# MOS-2.net
KiCad netlist of a schematic drawn in EAGLE
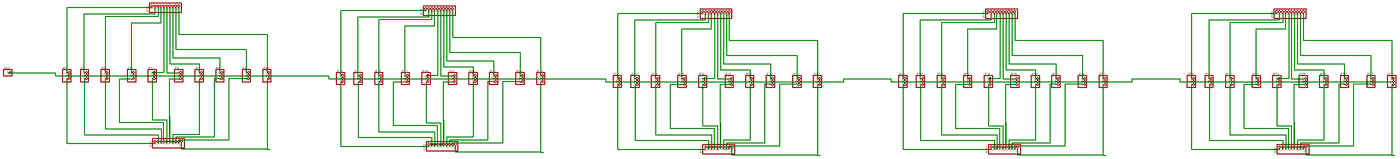
[diagram p0: schematic, sheet 1, overview]
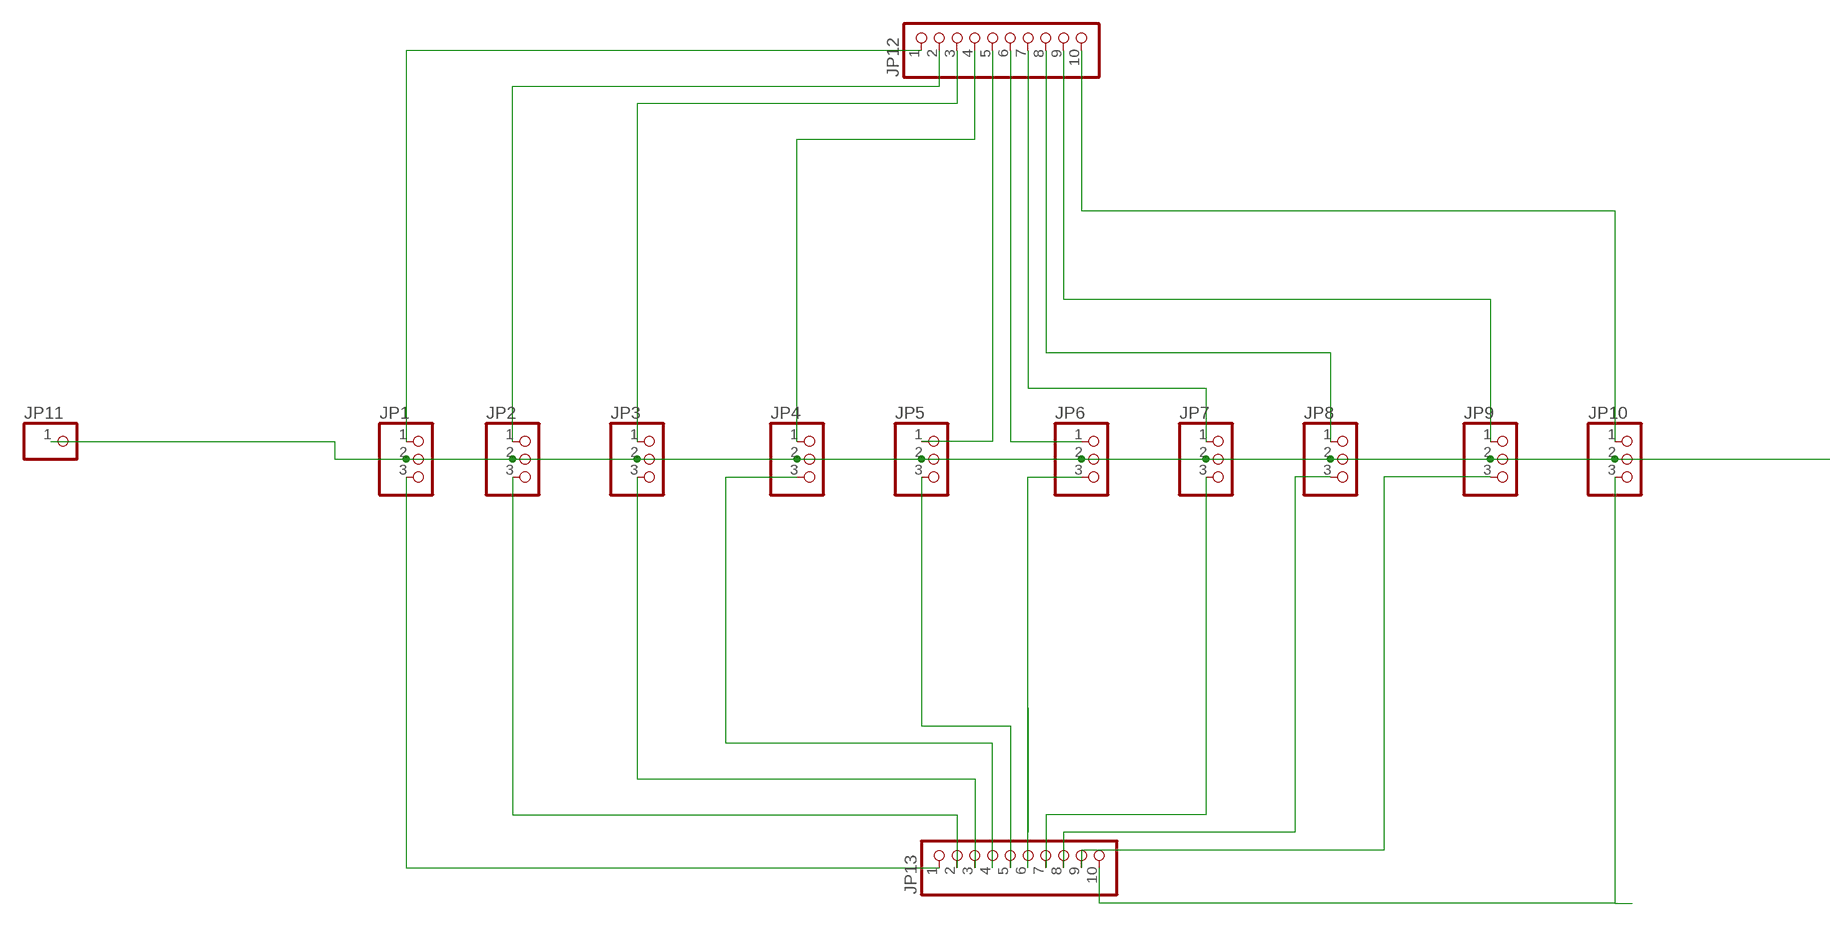
[diagram p1: schematic, sheet 1, part 1 of 4]
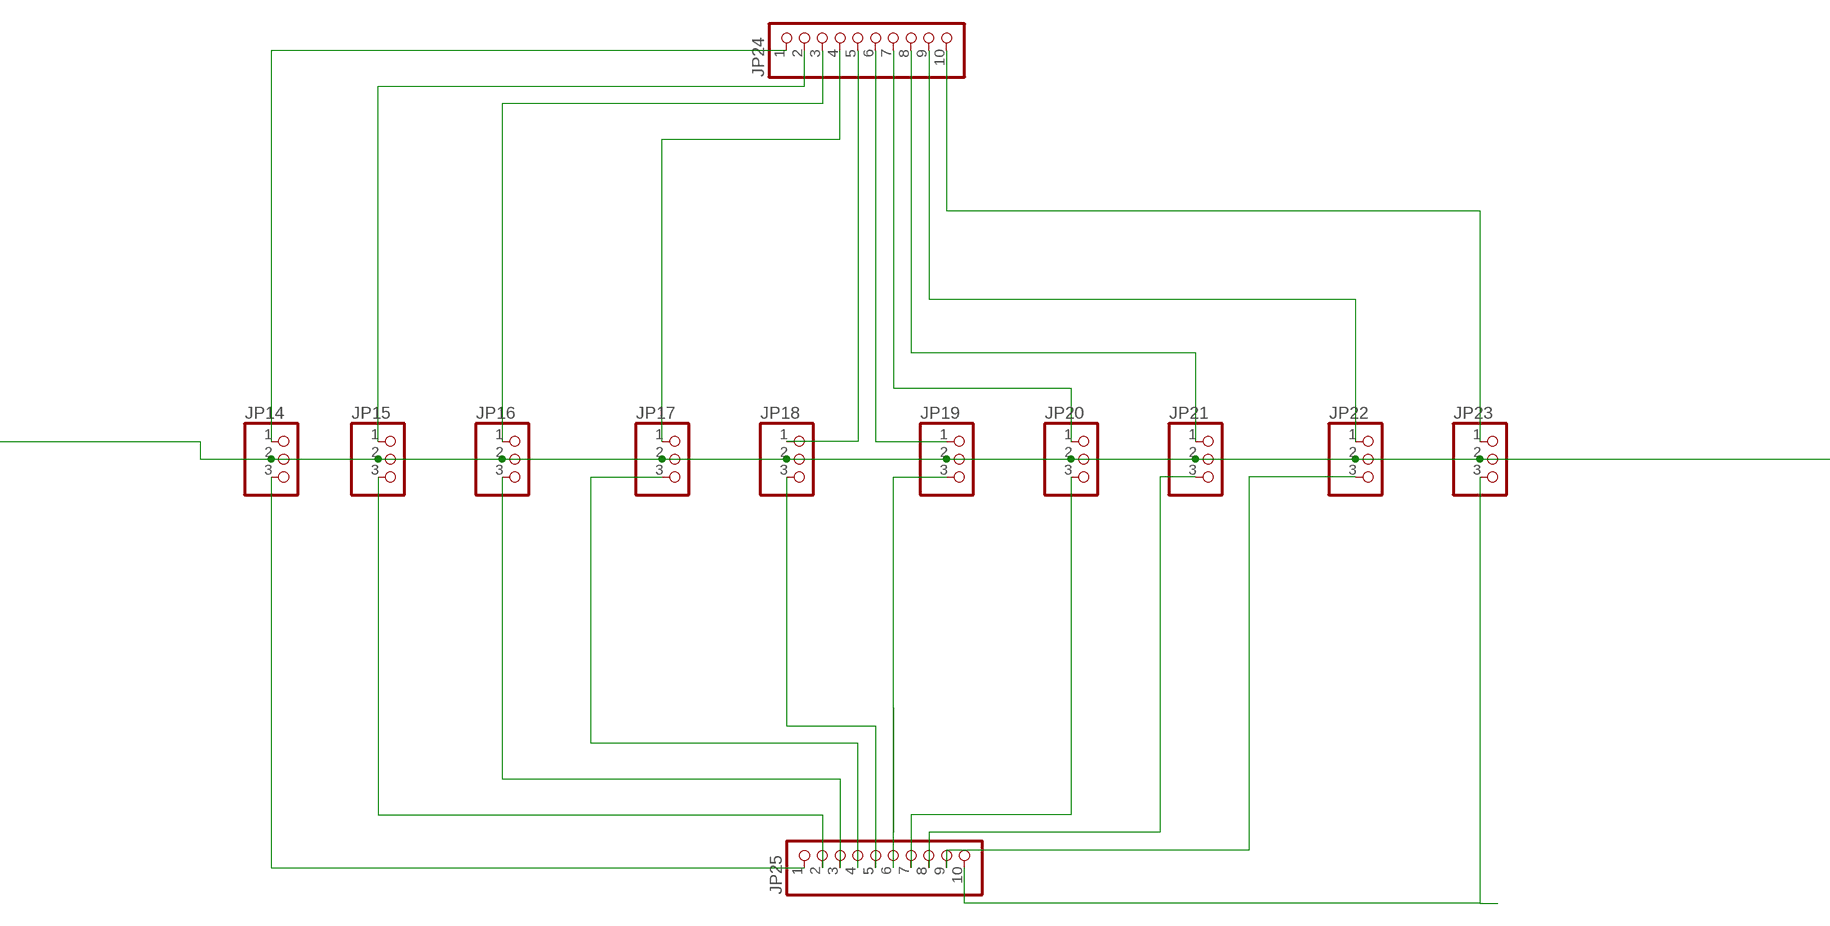
[diagram p2: schematic, sheet 1, part 2 of 4]
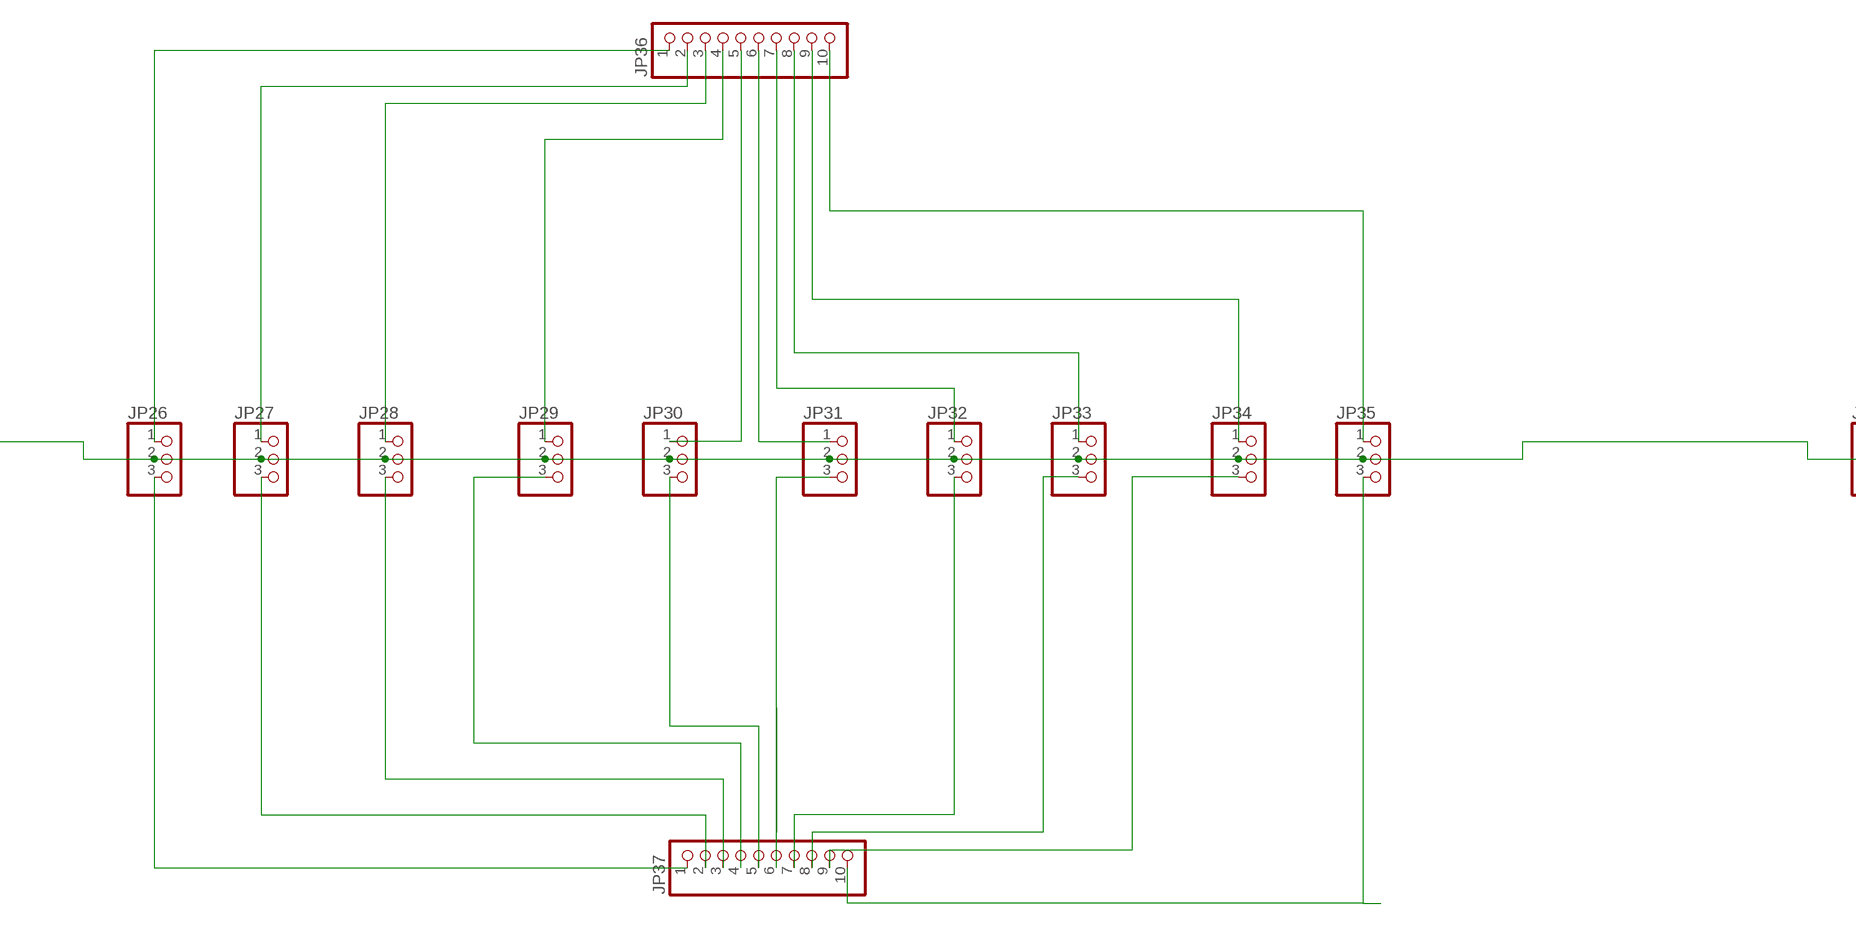
[diagram p3: schematic, sheet 1, part 3 of 4]
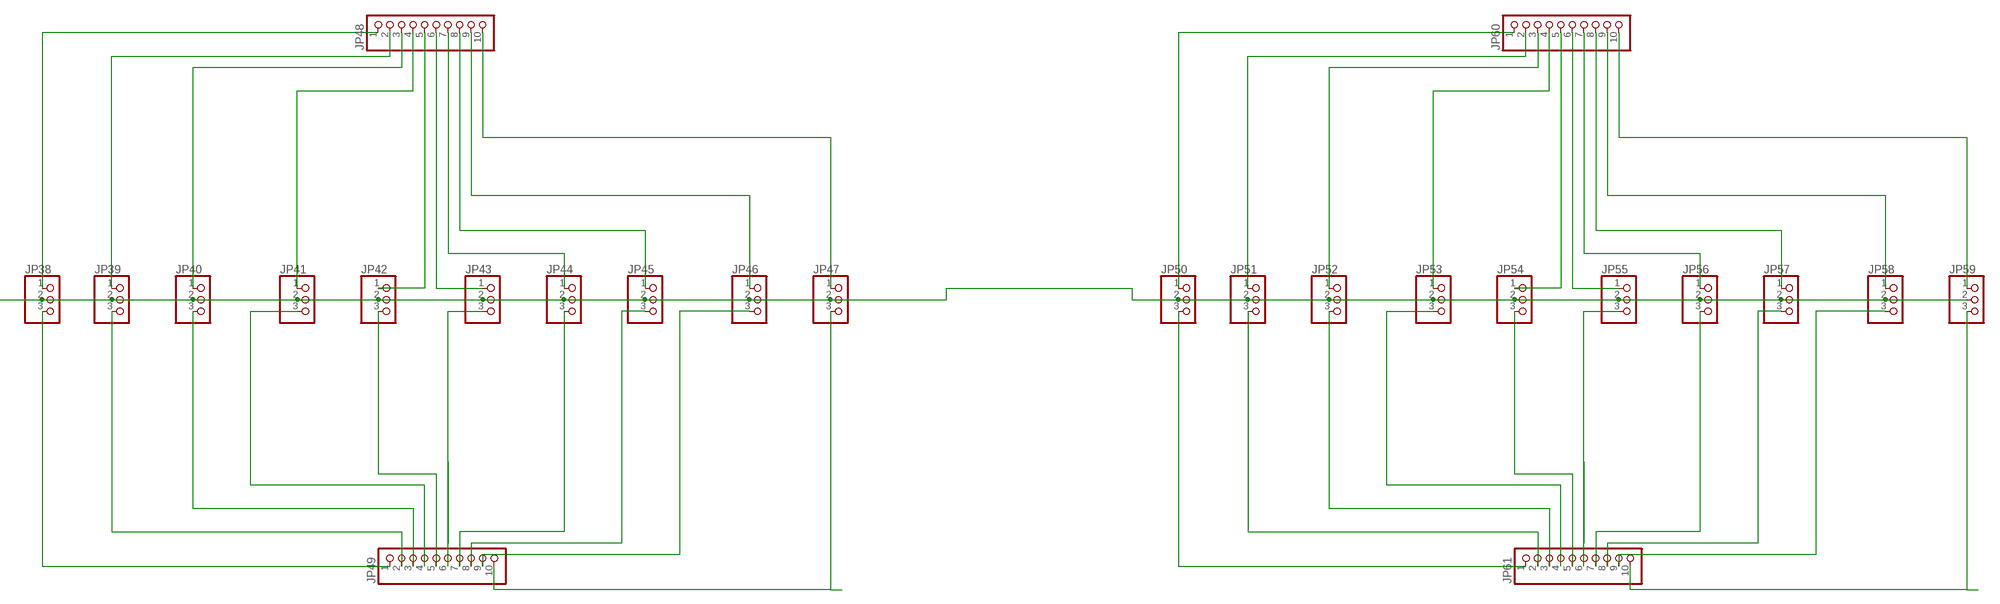
[diagram p4: schematic, sheet 1, part 4 of 4]

(export (version "E")
  (design (tool "Eeschema 10.0.6"))
  (components
    (comp (ref "JP1")
      (value "PINHD-1X3")
      (footprint "eagle-import:1X03")
      (libsource (lib "eagle-import") (part "PINHD-1X3"))
    )
    (comp (ref "JP2")
      (value "PINHD-1X3")
      (footprint "eagle-import:1X03")
      (libsource (lib "eagle-import") (part "PINHD-1X3"))
    )
    (comp (ref "JP3")
      (value "PINHD-1X3")
      (footprint "eagle-import:1X03")
      (libsource (lib "eagle-import") (part "PINHD-1X3"))
    )
    (comp (ref "JP4")
      (value "PINHD-1X3")
      (footprint "eagle-import:1X03")
      (libsource (lib "eagle-import") (part "PINHD-1X3"))
    )
    (comp (ref "JP5")
      (value "PINHD-1X3")
      (footprint "eagle-import:1X03")
      (libsource (lib "eagle-import") (part "PINHD-1X3"))
    )
    (comp (ref "JP6")
      (value "PINHD-1X3")
      (footprint "eagle-import:1X03")
      (libsource (lib "eagle-import") (part "PINHD-1X3"))
    )
    (comp (ref "JP7")
      (value "PINHD-1X3")
      (footprint "eagle-import:1X03")
      (libsource (lib "eagle-import") (part "PINHD-1X3"))
    )
    (comp (ref "JP8")
      (value "PINHD-1X3")
      (footprint "eagle-import:1X03")
      (libsource (lib "eagle-import") (part "PINHD-1X3"))
    )
    (comp (ref "JP9")
      (value "PINHD-1X3")
      (footprint "eagle-import:1X03")
      (libsource (lib "eagle-import") (part "PINHD-1X3"))
    )
    (comp (ref "JP10")
      (value "PINHD-1X3")
      (footprint "eagle-import:1X03")
      (libsource (lib "eagle-import") (part "PINHD-1X3"))
    )
    (comp (ref "JP11")
      (value "PINHD-1X1")
      (footprint "eagle-import:1X01")
      (libsource (lib "eagle-import") (part "PINHD-1X1"))
    )
    (comp (ref "JP12")
      (value "PINHD-1X10")
      (footprint "eagle-import:1X10")
      (libsource (lib "eagle-import") (part "PINHD-1X10"))
    )
    (comp (ref "JP13")
      (value "PINHD-1X10")
      (footprint "eagle-import:1X10")
      (libsource (lib "eagle-import") (part "PINHD-1X10"))
    )
    (comp (ref "JP14")
      (value "PINHD-1X3")
      (footprint "eagle-import:1X03")
      (libsource (lib "eagle-import") (part "PINHD-1X3"))
    )
    (comp (ref "JP15")
      (value "PINHD-1X3")
      (footprint "eagle-import:1X03")
      (libsource (lib "eagle-import") (part "PINHD-1X3"))
    )
    (comp (ref "JP16")
      (value "PINHD-1X3")
      (footprint "eagle-import:1X03")
      (libsource (lib "eagle-import") (part "PINHD-1X3"))
    )
    (comp (ref "JP17")
      (value "PINHD-1X3")
      (footprint "eagle-import:1X03")
      (libsource (lib "eagle-import") (part "PINHD-1X3"))
    )
    (comp (ref "JP18")
      (value "PINHD-1X3")
      (footprint "eagle-import:1X03")
      (libsource (lib "eagle-import") (part "PINHD-1X3"))
    )
    (comp (ref "JP19")
      (value "PINHD-1X3")
      (footprint "eagle-import:1X03")
      (libsource (lib "eagle-import") (part "PINHD-1X3"))
    )
    (comp (ref "JP20")
      (value "PINHD-1X3")
      (footprint "eagle-import:1X03")
      (libsource (lib "eagle-import") (part "PINHD-1X3"))
    )
    (comp (ref "JP21")
      (value "PINHD-1X3")
      (footprint "eagle-import:1X03")
      (libsource (lib "eagle-import") (part "PINHD-1X3"))
    )
    (comp (ref "JP22")
      (value "PINHD-1X3")
      (footprint "eagle-import:1X03")
      (libsource (lib "eagle-import") (part "PINHD-1X3"))
    )
    (comp (ref "JP23")
      (value "PINHD-1X3")
      (footprint "eagle-import:1X03")
      (libsource (lib "eagle-import") (part "PINHD-1X3"))
    )
    (comp (ref "JP24")
      (value "PINHD-1X10")
      (footprint "eagle-import:1X10")
      (libsource (lib "eagle-import") (part "PINHD-1X10"))
    )
    (comp (ref "JP25")
      (value "PINHD-1X10")
      (footprint "eagle-import:1X10")
      (libsource (lib "eagle-import") (part "PINHD-1X10"))
    )
    (comp (ref "JP26")
      (value "PINHD-1X3")
      (footprint "eagle-import:1X03")
      (libsource (lib "eagle-import") (part "PINHD-1X3"))
    )
    (comp (ref "JP27")
      (value "PINHD-1X3")
      (footprint "eagle-import:1X03")
      (libsource (lib "eagle-import") (part "PINHD-1X3"))
    )
    (comp (ref "JP28")
      (value "PINHD-1X3")
      (footprint "eagle-import:1X03")
      (libsource (lib "eagle-import") (part "PINHD-1X3"))
    )
    (comp (ref "JP29")
      (value "PINHD-1X3")
      (footprint "eagle-import:1X03")
      (libsource (lib "eagle-import") (part "PINHD-1X3"))
    )
    (comp (ref "JP30")
      (value "PINHD-1X3")
      (footprint "eagle-import:1X03")
      (libsource (lib "eagle-import") (part "PINHD-1X3"))
    )
    (comp (ref "JP31")
      (value "PINHD-1X3")
      (footprint "eagle-import:1X03")
      (libsource (lib "eagle-import") (part "PINHD-1X3"))
    )
    (comp (ref "JP32")
      (value "PINHD-1X3")
      (footprint "eagle-import:1X03")
      (libsource (lib "eagle-import") (part "PINHD-1X3"))
    )
    (comp (ref "JP33")
      (value "PINHD-1X3")
      (footprint "eagle-import:1X03")
      (libsource (lib "eagle-import") (part "PINHD-1X3"))
    )
    (comp (ref "JP34")
      (value "PINHD-1X3")
      (footprint "eagle-import:1X03")
      (libsource (lib "eagle-import") (part "PINHD-1X3"))
    )
    (comp (ref "JP35")
      (value "PINHD-1X3")
      (footprint "eagle-import:1X03")
      (libsource (lib "eagle-import") (part "PINHD-1X3"))
    )
    (comp (ref "JP36")
      (value "PINHD-1X10")
      (footprint "eagle-import:1X10")
      (libsource (lib "eagle-import") (part "PINHD-1X10"))
    )
    (comp (ref "JP37")
      (value "PINHD-1X10")
      (footprint "eagle-import:1X10")
      (libsource (lib "eagle-import") (part "PINHD-1X10"))
    )
    (comp (ref "JP38")
      (value "PINHD-1X3")
      (footprint "eagle-import:1X03")
      (libsource (lib "eagle-import") (part "PINHD-1X3"))
    )
    (comp (ref "JP39")
      (value "PINHD-1X3")
      (footprint "eagle-import:1X03")
      (libsource (lib "eagle-import") (part "PINHD-1X3"))
    )
    (comp (ref "JP40")
      (value "PINHD-1X3")
      (footprint "eagle-import:1X03")
      (libsource (lib "eagle-import") (part "PINHD-1X3"))
    )
    (comp (ref "JP41")
      (value "PINHD-1X3")
      (footprint "eagle-import:1X03")
      (libsource (lib "eagle-import") (part "PINHD-1X3"))
    )
    (comp (ref "JP42")
      (value "PINHD-1X3")
      (footprint "eagle-import:1X03")
      (libsource (lib "eagle-import") (part "PINHD-1X3"))
    )
    (comp (ref "JP43")
      (value "PINHD-1X3")
      (footprint "eagle-import:1X03")
      (libsource (lib "eagle-import") (part "PINHD-1X3"))
    )
    (comp (ref "JP44")
      (value "PINHD-1X3")
      (footprint "eagle-import:1X03")
      (libsource (lib "eagle-import") (part "PINHD-1X3"))
    )
    (comp (ref "JP45")
      (value "PINHD-1X3")
      (footprint "eagle-import:1X03")
      (libsource (lib "eagle-import") (part "PINHD-1X3"))
    )
    (comp (ref "JP46")
      (value "PINHD-1X3")
      (footprint "eagle-import:1X03")
      (libsource (lib "eagle-import") (part "PINHD-1X3"))
    )
    (comp (ref "JP47")
      (value "PINHD-1X3")
      (footprint "eagle-import:1X03")
      (libsource (lib "eagle-import") (part "PINHD-1X3"))
    )
    (comp (ref "JP48")
      (value "PINHD-1X10")
      (footprint "eagle-import:1X10")
      (libsource (lib "eagle-import") (part "PINHD-1X10"))
    )
    (comp (ref "JP49")
      (value "PINHD-1X10")
      (footprint "eagle-import:1X10")
      (libsource (lib "eagle-import") (part "PINHD-1X10"))
    )
    (comp (ref "JP50")
      (value "PINHD-1X3")
      (footprint "eagle-import:1X03")
      (libsource (lib "eagle-import") (part "PINHD-1X3"))
    )
    (comp (ref "JP51")
      (value "PINHD-1X3")
      (footprint "eagle-import:1X03")
      (libsource (lib "eagle-import") (part "PINHD-1X3"))
    )
    (comp (ref "JP52")
      (value "PINHD-1X3")
      (footprint "eagle-import:1X03")
      (libsource (lib "eagle-import") (part "PINHD-1X3"))
    )
    (comp (ref "JP53")
      (value "PINHD-1X3")
      (footprint "eagle-import:1X03")
      (libsource (lib "eagle-import") (part "PINHD-1X3"))
    )
    (comp (ref "JP54")
      (value "PINHD-1X3")
      (footprint "eagle-import:1X03")
      (libsource (lib "eagle-import") (part "PINHD-1X3"))
    )
    (comp (ref "JP55")
      (value "PINHD-1X3")
      (footprint "eagle-import:1X03")
      (libsource (lib "eagle-import") (part "PINHD-1X3"))
    )
    (comp (ref "JP56")
      (value "PINHD-1X3")
      (footprint "eagle-import:1X03")
      (libsource (lib "eagle-import") (part "PINHD-1X3"))
    )
    (comp (ref "JP57")
      (value "PINHD-1X3")
      (footprint "eagle-import:1X03")
      (libsource (lib "eagle-import") (part "PINHD-1X3"))
    )
    (comp (ref "JP58")
      (value "PINHD-1X3")
      (footprint "eagle-import:1X03")
      (libsource (lib "eagle-import") (part "PINHD-1X3"))
    )
    (comp (ref "JP59")
      (value "PINHD-1X3")
      (footprint "eagle-import:1X03")
      (libsource (lib "eagle-import") (part "PINHD-1X3"))
    )
    (comp (ref "JP60")
      (value "PINHD-1X10")
      (footprint "eagle-import:1X10")
      (libsource (lib "eagle-import") (part "PINHD-1X10"))
    )
    (comp (ref "JP61")
      (value "PINHD-1X10")
      (footprint "eagle-import:1X10")
      (libsource (lib "eagle-import") (part "PINHD-1X10"))
    )
  )
  (nets
    (net (code "1") (name "Net-(JP1-Pad1)") (class "Default")
      (node (ref "JP1") (pin "1") (pinfunction "1_1") (pintype "passive"))
      (node (ref "JP12") (pin "1") (pinfunction "1_1") (pintype "passive"))
    )
    (net (code "2") (name "Net-(JP1-Pad2)") (class "Default")
      (node (ref "JP1") (pin "2") (pinfunction "2_2") (pintype "passive"))
      (node (ref "JP10") (pin "2") (pinfunction "2_2") (pintype "passive"))
      (node (ref "JP11") (pin "1") (pinfunction "1_1") (pintype "passive"))
      (node (ref "JP14") (pin "2") (pinfunction "2_2") (pintype "passive"))
      (node (ref "JP15") (pin "2") (pinfunction "2_2") (pintype "passive"))
      (node (ref "JP16") (pin "2") (pinfunction "2_2") (pintype "passive"))
      (node (ref "JP17") (pin "2") (pinfunction "2_2") (pintype "passive"))
      (node (ref "JP18") (pin "2") (pinfunction "2_2") (pintype "passive"))
      (node (ref "JP19") (pin "2") (pinfunction "2_2") (pintype "passive"))
      (node (ref "JP2") (pin "2") (pinfunction "2_2") (pintype "passive"))
      (node (ref "JP20") (pin "2") (pinfunction "2_2") (pintype "passive"))
      (node (ref "JP21") (pin "2") (pinfunction "2_2") (pintype "passive"))
      (node (ref "JP22") (pin "2") (pinfunction "2_2") (pintype "passive"))
      (node (ref "JP23") (pin "2") (pinfunction "2_2") (pintype "passive"))
      (node (ref "JP26") (pin "2") (pinfunction "2_2") (pintype "passive"))
      (node (ref "JP27") (pin "2") (pinfunction "2_2") (pintype "passive"))
      (node (ref "JP28") (pin "2") (pinfunction "2_2") (pintype "passive"))
      (node (ref "JP29") (pin "2") (pinfunction "2_2") (pintype "passive"))
      (node (ref "JP3") (pin "2") (pinfunction "2_2") (pintype "passive"))
      (node (ref "JP30") (pin "2") (pinfunction "2_2") (pintype "passive"))
      (node (ref "JP31") (pin "2") (pinfunction "2_2") (pintype "passive"))
      (node (ref "JP32") (pin "2") (pinfunction "2_2") (pintype "passive"))
      (node (ref "JP33") (pin "2") (pinfunction "2_2") (pintype "passive"))
      (node (ref "JP34") (pin "2") (pinfunction "2_2") (pintype "passive"))
      (node (ref "JP35") (pin "2") (pinfunction "2_2") (pintype "passive"))
      (node (ref "JP38") (pin "2") (pinfunction "2_2") (pintype "passive"))
      (node (ref "JP39") (pin "2") (pinfunction "2_2") (pintype "passive"))
      (node (ref "JP4") (pin "2") (pinfunction "2_2") (pintype "passive"))
      (node (ref "JP40") (pin "2") (pinfunction "2_2") (pintype "passive"))
      (node (ref "JP41") (pin "2") (pinfunction "2_2") (pintype "passive"))
      (node (ref "JP42") (pin "2") (pinfunction "2_2") (pintype "passive"))
      (node (ref "JP43") (pin "2") (pinfunction "2_2") (pintype "passive"))
      (node (ref "JP44") (pin "2") (pinfunction "2_2") (pintype "passive"))
      (node (ref "JP45") (pin "2") (pinfunction "2_2") (pintype "passive"))
      (node (ref "JP46") (pin "2") (pinfunction "2_2") (pintype "passive"))
      (node (ref "JP47") (pin "2") (pinfunction "2_2") (pintype "passive"))
      (node (ref "JP5") (pin "2") (pinfunction "2_2") (pintype "passive"))
      (node (ref "JP50") (pin "2") (pinfunction "2_2") (pintype "passive"))
      (node (ref "JP51") (pin "2") (pinfunction "2_2") (pintype "passive"))
      (node (ref "JP52") (pin "2") (pinfunction "2_2") (pintype "passive"))
      (node (ref "JP53") (pin "2") (pinfunction "2_2") (pintype "passive"))
      (node (ref "JP54") (pin "2") (pinfunction "2_2") (pintype "passive"))
      (node (ref "JP55") (pin "2") (pinfunction "2_2") (pintype "passive"))
      (node (ref "JP56") (pin "2") (pinfunction "2_2") (pintype "passive"))
      (node (ref "JP57") (pin "2") (pinfunction "2_2") (pintype "passive"))
      (node (ref "JP58") (pin "2") (pinfunction "2_2") (pintype "passive"))
      (node (ref "JP59") (pin "2") (pinfunction "2_2") (pintype "passive"))
      (node (ref "JP6") (pin "2") (pinfunction "2_2") (pintype "passive"))
      (node (ref "JP7") (pin "2") (pinfunction "2_2") (pintype "passive"))
      (node (ref "JP8") (pin "2") (pinfunction "2_2") (pintype "passive"))
      (node (ref "JP9") (pin "2") (pinfunction "2_2") (pintype "passive"))
    )
    (net (code "3") (name "Net-(JP1-Pad3)") (class "Default")
      (node (ref "JP1") (pin "3") (pinfunction "3_3") (pintype "passive"))
      (node (ref "JP13") (pin "1") (pinfunction "1_1") (pintype "passive"))
    )
    (net (code "4") (name "Net-(JP10-Pad1)") (class "Default")
      (node (ref "JP10") (pin "1") (pinfunction "1_1") (pintype "passive"))
      (node (ref "JP12") (pin "10") (pinfunction "10_10") (pintype "passive"))
    )
    (net (code "5") (name "Net-(JP10-Pad3)") (class "Default")
      (node (ref "JP10") (pin "3") (pinfunction "3_3") (pintype "passive"))
      (node (ref "JP13") (pin "10") (pinfunction "10_10") (pintype "passive"))
    )
    (net (code "6") (name "Net-(JP12-Pad2)") (class "Default")
      (node (ref "JP12") (pin "2") (pinfunction "2_2") (pintype "passive"))
      (node (ref "JP2") (pin "1") (pinfunction "1_1") (pintype "passive"))
    )
    (net (code "7") (name "Net-(JP12-Pad3)") (class "Default")
      (node (ref "JP12") (pin "3") (pinfunction "3_3") (pintype "passive"))
      (node (ref "JP3") (pin "1") (pinfunction "1_1") (pintype "passive"))
    )
    (net (code "8") (name "Net-(JP12-Pad4)") (class "Default")
      (node (ref "JP12") (pin "4") (pinfunction "4_4") (pintype "passive"))
      (node (ref "JP4") (pin "1") (pinfunction "1_1") (pintype "passive"))
    )
    (net (code "9") (name "Net-(JP12-Pad5)") (class "Default")
      (node (ref "JP12") (pin "5") (pinfunction "5_5") (pintype "passive"))
      (node (ref "JP5") (pin "1") (pinfunction "1_1") (pintype "passive"))
    )
    (net (code "10") (name "Net-(JP12-Pad6)") (class "Default")
      (node (ref "JP12") (pin "6") (pinfunction "6_6") (pintype "passive"))
      (node (ref "JP6") (pin "1") (pinfunction "1_1") (pintype "passive"))
    )
    (net (code "11") (name "Net-(JP12-Pad7)") (class "Default")
      (node (ref "JP12") (pin "7") (pinfunction "7_7") (pintype "passive"))
      (node (ref "JP7") (pin "1") (pinfunction "1_1") (pintype "passive"))
    )
    (net (code "12") (name "Net-(JP12-Pad8)") (class "Default")
      (node (ref "JP12") (pin "8") (pinfunction "8_8") (pintype "passive"))
      (node (ref "JP8") (pin "1") (pinfunction "1_1") (pintype "passive"))
    )
    (net (code "13") (name "Net-(JP12-Pad9)") (class "Default")
      (node (ref "JP12") (pin "9") (pinfunction "9_9") (pintype "passive"))
      (node (ref "JP9") (pin "1") (pinfunction "1_1") (pintype "passive"))
    )
    (net (code "14") (name "Net-(JP13-Pad2)") (class "Default")
      (node (ref "JP13") (pin "2") (pinfunction "2_2") (pintype "passive"))
      (node (ref "JP2") (pin "3") (pinfunction "3_3") (pintype "passive"))
    )
    (net (code "15") (name "Net-(JP13-Pad3)") (class "Default")
      (node (ref "JP13") (pin "3") (pinfunction "3_3") (pintype "passive"))
      (node (ref "JP3") (pin "3") (pinfunction "3_3") (pintype "passive"))
    )
    (net (code "16") (name "Net-(JP13-Pad4)") (class "Default")
      (node (ref "JP13") (pin "4") (pinfunction "4_4") (pintype "passive"))
      (node (ref "JP4") (pin "3") (pinfunction "3_3") (pintype "passive"))
    )
    (net (code "17") (name "Net-(JP13-Pad5)") (class "Default")
      (node (ref "JP13") (pin "5") (pinfunction "5_5") (pintype "passive"))
      (node (ref "JP5") (pin "3") (pinfunction "3_3") (pintype "passive"))
    )
    (net (code "18") (name "Net-(JP13-Pad6)") (class "Default")
      (node (ref "JP13") (pin "6") (pinfunction "6_6") (pintype "passive"))
      (node (ref "JP6") (pin "3") (pinfunction "3_3") (pintype "passive"))
    )
    (net (code "19") (name "Net-(JP13-Pad7)") (class "Default")
      (node (ref "JP13") (pin "7") (pinfunction "7_7") (pintype "passive"))
      (node (ref "JP7") (pin "3") (pinfunction "3_3") (pintype "passive"))
    )
    (net (code "20") (name "Net-(JP13-Pad8)") (class "Default")
      (node (ref "JP13") (pin "8") (pinfunction "8_8") (pintype "passive"))
      (node (ref "JP8") (pin "3") (pinfunction "3_3") (pintype "passive"))
    )
    (net (code "21") (name "Net-(JP13-Pad9)") (class "Default")
      (node (ref "JP13") (pin "9") (pinfunction "9_9") (pintype "passive"))
      (node (ref "JP9") (pin "3") (pinfunction "3_3") (pintype "passive"))
    )
    (net (code "22") (name "Net-(JP14-Pad1)") (class "Default")
      (node (ref "JP14") (pin "1") (pinfunction "1_1") (pintype "passive"))
      (node (ref "JP24") (pin "1") (pinfunction "1_1") (pintype "passive"))
    )
    (net (code "23") (name "Net-(JP14-Pad3)") (class "Default")
      (node (ref "JP14") (pin "3") (pinfunction "3_3") (pintype "passive"))
      (node (ref "JP25") (pin "1") (pinfunction "1_1") (pintype "passive"))
    )
    (net (code "24") (name "Net-(JP15-Pad1)") (class "Default")
      (node (ref "JP15") (pin "1") (pinfunction "1_1") (pintype "passive"))
      (node (ref "JP24") (pin "2") (pinfunction "2_2") (pintype "passive"))
    )
    (net (code "25") (name "Net-(JP15-Pad3)") (class "Default")
      (node (ref "JP15") (pin "3") (pinfunction "3_3") (pintype "passive"))
      (node (ref "JP25") (pin "2") (pinfunction "2_2") (pintype "passive"))
    )
    (net (code "26") (name "Net-(JP16-Pad1)") (class "Default")
      (node (ref "JP16") (pin "1") (pinfunction "1_1") (pintype "passive"))
      (node (ref "JP24") (pin "3") (pinfunction "3_3") (pintype "passive"))
    )
    (net (code "27") (name "Net-(JP16-Pad3)") (class "Default")
      (node (ref "JP16") (pin "3") (pinfunction "3_3") (pintype "passive"))
      (node (ref "JP25") (pin "3") (pinfunction "3_3") (pintype "passive"))
    )
    (net (code "28") (name "Net-(JP17-Pad1)") (class "Default")
      (node (ref "JP17") (pin "1") (pinfunction "1_1") (pintype "passive"))
      (node (ref "JP24") (pin "4") (pinfunction "4_4") (pintype "passive"))
    )
    (net (code "29") (name "Net-(JP17-Pad3)") (class "Default")
      (node (ref "JP17") (pin "3") (pinfunction "3_3") (pintype "passive"))
      (node (ref "JP25") (pin "4") (pinfunction "4_4") (pintype "passive"))
    )
    (net (code "30") (name "Net-(JP18-Pad1)") (class "Default")
      (node (ref "JP18") (pin "1") (pinfunction "1_1") (pintype "passive"))
      (node (ref "JP24") (pin "5") (pinfunction "5_5") (pintype "passive"))
    )
    (net (code "31") (name "Net-(JP18-Pad3)") (class "Default")
      (node (ref "JP18") (pin "3") (pinfunction "3_3") (pintype "passive"))
      (node (ref "JP25") (pin "5") (pinfunction "5_5") (pintype "passive"))
    )
    (net (code "32") (name "Net-(JP19-Pad1)") (class "Default")
      (node (ref "JP19") (pin "1") (pinfunction "1_1") (pintype "passive"))
      (node (ref "JP24") (pin "6") (pinfunction "6_6") (pintype "passive"))
    )
    (net (code "33") (name "Net-(JP19-Pad3)") (class "Default")
      (node (ref "JP19") (pin "3") (pinfunction "3_3") (pintype "passive"))
      (node (ref "JP25") (pin "6") (pinfunction "6_6") (pintype "passive"))
    )
    (net (code "34") (name "Net-(JP20-Pad1)") (class "Default")
      (node (ref "JP20") (pin "1") (pinfunction "1_1") (pintype "passive"))
      (node (ref "JP24") (pin "7") (pinfunction "7_7") (pintype "passive"))
    )
    (net (code "35") (name "Net-(JP20-Pad3)") (class "Default")
      (node (ref "JP20") (pin "3") (pinfunction "3_3") (pintype "passive"))
      (node (ref "JP25") (pin "7") (pinfunction "7_7") (pintype "passive"))
    )
    (net (code "36") (name "Net-(JP21-Pad1)") (class "Default")
      (node (ref "JP21") (pin "1") (pinfunction "1_1") (pintype "passive"))
      (node (ref "JP24") (pin "8") (pinfunction "8_8") (pintype "passive"))
    )
    (net (code "37") (name "Net-(JP21-Pad3)") (class "Default")
      (node (ref "JP21") (pin "3") (pinfunction "3_3") (pintype "passive"))
      (node (ref "JP25") (pin "8") (pinfunction "8_8") (pintype "passive"))
    )
    (net (code "38") (name "Net-(JP22-Pad1)") (class "Default")
      (node (ref "JP22") (pin "1") (pinfunction "1_1") (pintype "passive"))
      (node (ref "JP24") (pin "9") (pinfunction "9_9") (pintype "passive"))
    )
    (net (code "39") (name "Net-(JP22-Pad3)") (class "Default")
      (node (ref "JP22") (pin "3") (pinfunction "3_3") (pintype "passive"))
      (node (ref "JP25") (pin "9") (pinfunction "9_9") (pintype "passive"))
    )
    (net (code "40") (name "Net-(JP23-Pad1)") (class "Default")
      (node (ref "JP23") (pin "1") (pinfunction "1_1") (pintype "passive"))
      (node (ref "JP24") (pin "10") (pinfunction "10_10") (pintype "passive"))
    )
    (net (code "41") (name "Net-(JP23-Pad3)") (class "Default")
      (node (ref "JP23") (pin "3") (pinfunction "3_3") (pintype "passive"))
      (node (ref "JP25") (pin "10") (pinfunction "10_10") (pintype "passive"))
    )
    (net (code "42") (name "Net-(JP26-Pad1)") (class "Default")
      (node (ref "JP26") (pin "1") (pinfunction "1_1") (pintype "passive"))
      (node (ref "JP36") (pin "1") (pinfunction "1_1") (pintype "passive"))
    )
    (net (code "43") (name "Net-(JP26-Pad3)") (class "Default")
      (node (ref "JP26") (pin "3") (pinfunction "3_3") (pintype "passive"))
      (node (ref "JP37") (pin "1") (pinfunction "1_1") (pintype "passive"))
    )
    (net (code "44") (name "Net-(JP27-Pad1)") (class "Default")
      (node (ref "JP27") (pin "1") (pinfunction "1_1") (pintype "passive"))
      (node (ref "JP36") (pin "2") (pinfunction "2_2") (pintype "passive"))
    )
    (net (code "45") (name "Net-(JP27-Pad3)") (class "Default")
      (node (ref "JP27") (pin "3") (pinfunction "3_3") (pintype "passive"))
      (node (ref "JP37") (pin "2") (pinfunction "2_2") (pintype "passive"))
    )
    (net (code "46") (name "Net-(JP28-Pad1)") (class "Default")
      (node (ref "JP28") (pin "1") (pinfunction "1_1") (pintype "passive"))
      (node (ref "JP36") (pin "3") (pinfunction "3_3") (pintype "passive"))
    )
    (net (code "47") (name "Net-(JP28-Pad3)") (class "Default")
      (node (ref "JP28") (pin "3") (pinfunction "3_3") (pintype "passive"))
      (node (ref "JP37") (pin "3") (pinfunction "3_3") (pintype "passive"))
    )
    (net (code "48") (name "Net-(JP29-Pad1)") (class "Default")
      (node (ref "JP29") (pin "1") (pinfunction "1_1") (pintype "passive"))
      (node (ref "JP36") (pin "4") (pinfunction "4_4") (pintype "passive"))
    )
    (net (code "49") (name "Net-(JP29-Pad3)") (class "Default")
      (node (ref "JP29") (pin "3") (pinfunction "3_3") (pintype "passive"))
      (node (ref "JP37") (pin "4") (pinfunction "4_4") (pintype "passive"))
    )
    (net (code "50") (name "Net-(JP30-Pad1)") (class "Default")
      (node (ref "JP30") (pin "1") (pinfunction "1_1") (pintype "passive"))
      (node (ref "JP36") (pin "5") (pinfunction "5_5") (pintype "passive"))
    )
    (net (code "51") (name "Net-(JP30-Pad3)") (class "Default")
      (node (ref "JP30") (pin "3") (pinfunction "3_3") (pintype "passive"))
      (node (ref "JP37") (pin "5") (pinfunction "5_5") (pintype "passive"))
    )
    (net (code "52") (name "Net-(JP31-Pad1)") (class "Default")
      (node (ref "JP31") (pin "1") (pinfunction "1_1") (pintype "passive"))
      (node (ref "JP36") (pin "6") (pinfunction "6_6") (pintype "passive"))
    )
    (net (code "53") (name "Net-(JP31-Pad3)") (class "Default")
      (node (ref "JP31") (pin "3") (pinfunction "3_3") (pintype "passive"))
      (node (ref "JP37") (pin "6") (pinfunction "6_6") (pintype "passive"))
    )
    (net (code "54") (name "Net-(JP32-Pad1)") (class "Default")
      (node (ref "JP32") (pin "1") (pinfunction "1_1") (pintype "passive"))
      (node (ref "JP36") (pin "7") (pinfunction "7_7") (pintype "passive"))
    )
    (net (code "55") (name "Net-(JP32-Pad3)") (class "Default")
      (node (ref "JP32") (pin "3") (pinfunction "3_3") (pintype "passive"))
      (node (ref "JP37") (pin "7") (pinfunction "7_7") (pintype "passive"))
    )
    (net (code "56") (name "Net-(JP33-Pad1)") (class "Default")
      (node (ref "JP33") (pin "1") (pinfunction "1_1") (pintype "passive"))
      (node (ref "JP36") (pin "8") (pinfunction "8_8") (pintype "passive"))
    )
    (net (code "57") (name "Net-(JP33-Pad3)") (class "Default")
      (node (ref "JP33") (pin "3") (pinfunction "3_3") (pintype "passive"))
      (node (ref "JP37") (pin "8") (pinfunction "8_8") (pintype "passive"))
    )
    (net (code "58") (name "Net-(JP34-Pad1)") (class "Default")
      (node (ref "JP34") (pin "1") (pinfunction "1_1") (pintype "passive"))
      (node (ref "JP36") (pin "9") (pinfunction "9_9") (pintype "passive"))
    )
    (net (code "59") (name "Net-(JP34-Pad3)") (class "Default")
      (node (ref "JP34") (pin "3") (pinfunction "3_3") (pintype "passive"))
      (node (ref "JP37") (pin "9") (pinfunction "9_9") (pintype "passive"))
    )
    (net (code "60") (name "Net-(JP35-Pad1)") (class "Default")
      (node (ref "JP35") (pin "1") (pinfunction "1_1") (pintype "passive"))
      (node (ref "JP36") (pin "10") (pinfunction "10_10") (pintype "passive"))
    )
    (net (code "61") (name "Net-(JP35-Pad3)") (class "Default")
      (node (ref "JP35") (pin "3") (pinfunction "3_3") (pintype "passive"))
      (node (ref "JP37") (pin "10") (pinfunction "10_10") (pintype "passive"))
    )
    (net (code "62") (name "Net-(JP38-Pad1)") (class "Default")
      (node (ref "JP38") (pin "1") (pinfunction "1_1") (pintype "passive"))
      (node (ref "JP48") (pin "1") (pinfunction "1_1") (pintype "passive"))
    )
    (net (code "63") (name "Net-(JP38-Pad3)") (class "Default")
      (node (ref "JP38") (pin "3") (pinfunction "3_3") (pintype "passive"))
      (node (ref "JP49") (pin "1") (pinfunction "1_1") (pintype "passive"))
    )
    (net (code "64") (name "Net-(JP39-Pad1)") (class "Default")
      (node (ref "JP39") (pin "1") (pinfunction "1_1") (pintype "passive"))
      (node (ref "JP48") (pin "2") (pinfunction "2_2") (pintype "passive"))
    )
    (net (code "65") (name "Net-(JP39-Pad3)") (class "Default")
      (node (ref "JP39") (pin "3") (pinfunction "3_3") (pintype "passive"))
      (node (ref "JP49") (pin "2") (pinfunction "2_2") (pintype "passive"))
    )
    (net (code "66") (name "Net-(JP40-Pad1)") (class "Default")
      (node (ref "JP40") (pin "1") (pinfunction "1_1") (pintype "passive"))
      (node (ref "JP48") (pin "3") (pinfunction "3_3") (pintype "passive"))
    )
    (net (code "67") (name "Net-(JP40-Pad3)") (class "Default")
      (node (ref "JP40") (pin "3") (pinfunction "3_3") (pintype "passive"))
      (node (ref "JP49") (pin "3") (pinfunction "3_3") (pintype "passive"))
    )
    (net (code "68") (name "Net-(JP41-Pad1)") (class "Default")
      (node (ref "JP41") (pin "1") (pinfunction "1_1") (pintype "passive"))
      (node (ref "JP48") (pin "4") (pinfunction "4_4") (pintype "passive"))
    )
    (net (code "69") (name "Net-(JP41-Pad3)") (class "Default")
      (node (ref "JP41") (pin "3") (pinfunction "3_3") (pintype "passive"))
      (node (ref "JP49") (pin "4") (pinfunction "4_4") (pintype "passive"))
    )
    (net (code "70") (name "Net-(JP42-Pad1)") (class "Default")
      (node (ref "JP42") (pin "1") (pinfunction "1_1") (pintype "passive"))
      (node (ref "JP48") (pin "5") (pinfunction "5_5") (pintype "passive"))
    )
    (net (code "71") (name "Net-(JP42-Pad3)") (class "Default")
      (node (ref "JP42") (pin "3") (pinfunction "3_3") (pintype "passive"))
      (node (ref "JP49") (pin "5") (pinfunction "5_5") (pintype "passive"))
    )
    (net (code "72") (name "Net-(JP43-Pad1)") (class "Default")
      (node (ref "JP43") (pin "1") (pinfunction "1_1") (pintype "passive"))
      (node (ref "JP48") (pin "6") (pinfunction "6_6") (pintype "passive"))
    )
    (net (code "73") (name "Net-(JP43-Pad3)") (class "Default")
      (node (ref "JP43") (pin "3") (pinfunction "3_3") (pintype "passive"))
      (node (ref "JP49") (pin "6") (pinfunction "6_6") (pintype "passive"))
    )
    (net (code "74") (name "Net-(JP44-Pad1)") (class "Default")
      (node (ref "JP44") (pin "1") (pinfunction "1_1") (pintype "passive"))
      (node (ref "JP48") (pin "7") (pinfunction "7_7") (pintype "passive"))
    )
    (net (code "75") (name "Net-(JP44-Pad3)") (class "Default")
      (node (ref "JP44") (pin "3") (pinfunction "3_3") (pintype "passive"))
      (node (ref "JP49") (pin "7") (pinfunction "7_7") (pintype "passive"))
    )
    (net (code "76") (name "Net-(JP45-Pad1)") (class "Default")
      (node (ref "JP45") (pin "1") (pinfunction "1_1") (pintype "passive"))
      (node (ref "JP48") (pin "8") (pinfunction "8_8") (pintype "passive"))
    )
    (net (code "77") (name "Net-(JP45-Pad3)") (class "Default")
      (node (ref "JP45") (pin "3") (pinfunction "3_3") (pintype "passive"))
      (node (ref "JP49") (pin "8") (pinfunction "8_8") (pintype "passive"))
    )
    (net (code "78") (name "Net-(JP46-Pad1)") (class "Default")
      (node (ref "JP46") (pin "1") (pinfunction "1_1") (pintype "passive"))
      (node (ref "JP48") (pin "9") (pinfunction "9_9") (pintype "passive"))
    )
    (net (code "79") (name "Net-(JP46-Pad3)") (class "Default")
      (node (ref "JP46") (pin "3") (pinfunction "3_3") (pintype "passive"))
      (node (ref "JP49") (pin "9") (pinfunction "9_9") (pintype "passive"))
    )
    (net (code "80") (name "Net-(JP47-Pad1)") (class "Default")
      (node (ref "JP47") (pin "1") (pinfunction "1_1") (pintype "passive"))
      (node (ref "JP48") (pin "10") (pinfunction "10_10") (pintype "passive"))
    )
    (net (code "81") (name "Net-(JP47-Pad3)") (class "Default")
      (node (ref "JP47") (pin "3") (pinfunction "3_3") (pintype "passive"))
      (node (ref "JP49") (pin "10") (pinfunction "10_10") (pintype "passive"))
    )
    (net (code "82") (name "Net-(JP50-Pad1)") (class "Default")
      (node (ref "JP50") (pin "1") (pinfunction "1_1") (pintype "passive"))
      (node (ref "JP60") (pin "1") (pinfunction "1_1") (pintype "passive"))
    )
    (net (code "83") (name "Net-(JP50-Pad3)") (class "Default")
      (node (ref "JP50") (pin "3") (pinfunction "3_3") (pintype "passive"))
      (node (ref "JP61") (pin "1") (pinfunction "1_1") (pintype "passive"))
    )
    (net (code "84") (name "Net-(JP51-Pad1)") (class "Default")
      (node (ref "JP51") (pin "1") (pinfunction "1_1") (pintype "passive"))
      (node (ref "JP60") (pin "2") (pinfunction "2_2") (pintype "passive"))
    )
    (net (code "85") (name "Net-(JP51-Pad3)") (class "Default")
      (node (ref "JP51") (pin "3") (pinfunction "3_3") (pintype "passive"))
      (node (ref "JP61") (pin "2") (pinfunction "2_2") (pintype "passive"))
    )
    (net (code "86") (name "Net-(JP52-Pad1)") (class "Default")
      (node (ref "JP52") (pin "1") (pinfunction "1_1") (pintype "passive"))
      (node (ref "JP60") (pin "3") (pinfunction "3_3") (pintype "passive"))
    )
    (net (code "87") (name "Net-(JP52-Pad3)") (class "Default")
      (node (ref "JP52") (pin "3") (pinfunction "3_3") (pintype "passive"))
      (node (ref "JP61") (pin "3") (pinfunction "3_3") (pintype "passive"))
    )
    (net (code "88") (name "Net-(JP53-Pad1)") (class "Default")
      (node (ref "JP53") (pin "1") (pinfunction "1_1") (pintype "passive"))
      (node (ref "JP60") (pin "4") (pinfunction "4_4") (pintype "passive"))
    )
    (net (code "89") (name "Net-(JP53-Pad3)") (class "Default")
      (node (ref "JP53") (pin "3") (pinfunction "3_3") (pintype "passive"))
      (node (ref "JP61") (pin "4") (pinfunction "4_4") (pintype "passive"))
    )
    (net (code "90") (name "Net-(JP54-Pad1)") (class "Default")
      (node (ref "JP54") (pin "1") (pinfunction "1_1") (pintype "passive"))
      (node (ref "JP60") (pin "5") (pinfunction "5_5") (pintype "passive"))
    )
    (net (code "91") (name "Net-(JP54-Pad3)") (class "Default")
      (node (ref "JP54") (pin "3") (pinfunction "3_3") (pintype "passive"))
      (node (ref "JP61") (pin "5") (pinfunction "5_5") (pintype "passive"))
    )
    (net (code "92") (name "Net-(JP55-Pad1)") (class "Default")
      (node (ref "JP55") (pin "1") (pinfunction "1_1") (pintype "passive"))
      (node (ref "JP60") (pin "6") (pinfunction "6_6") (pintype "passive"))
    )
    (net (code "93") (name "Net-(JP55-Pad3)") (class "Default")
      (node (ref "JP55") (pin "3") (pinfunction "3_3") (pintype "passive"))
      (node (ref "JP61") (pin "6") (pinfunction "6_6") (pintype "passive"))
    )
    (net (code "94") (name "Net-(JP56-Pad1)") (class "Default")
      (node (ref "JP56") (pin "1") (pinfunction "1_1") (pintype "passive"))
      (node (ref "JP60") (pin "7") (pinfunction "7_7") (pintype "passive"))
    )
    (net (code "95") (name "Net-(JP56-Pad3)") (class "Default")
      (node (ref "JP56") (pin "3") (pinfunction "3_3") (pintype "passive"))
      (node (ref "JP61") (pin "7") (pinfunction "7_7") (pintype "passive"))
    )
    (net (code "96") (name "Net-(JP57-Pad1)") (class "Default")
      (node (ref "JP57") (pin "1") (pinfunction "1_1") (pintype "passive"))
      (node (ref "JP60") (pin "8") (pinfunction "8_8") (pintype "passive"))
    )
    (net (code "97") (name "Net-(JP57-Pad3)") (class "Default")
      (node (ref "JP57") (pin "3") (pinfunction "3_3") (pintype "passive"))
      (node (ref "JP61") (pin "8") (pinfunction "8_8") (pintype "passive"))
    )
    (net (code "98") (name "Net-(JP58-Pad1)") (class "Default")
      (node (ref "JP58") (pin "1") (pinfunction "1_1") (pintype "passive"))
      (node (ref "JP60") (pin "9") (pinfunction "9_9") (pintype "passive"))
    )
    (net (code "99") (name "Net-(JP58-Pad3)") (class "Default")
      (node (ref "JP58") (pin "3") (pinfunction "3_3") (pintype "passive"))
      (node (ref "JP61") (pin "9") (pinfunction "9_9") (pintype "passive"))
    )
    (net (code "100") (name "Net-(JP59-Pad1)") (class "Default")
      (node (ref "JP59") (pin "1") (pinfunction "1_1") (pintype "passive"))
      (node (ref "JP60") (pin "10") (pinfunction "10_10") (pintype "passive"))
    )
    (net (code "101") (name "Net-(JP59-Pad3)") (class "Default")
      (node (ref "JP59") (pin "3") (pinfunction "3_3") (pintype "passive"))
      (node (ref "JP61") (pin "10") (pinfunction "10_10") (pintype "passive"))
    )
  )
)
